# Ref_2V048_LM4132AMF.net
KiCad netlist of a schematic drawn in Altium Designer
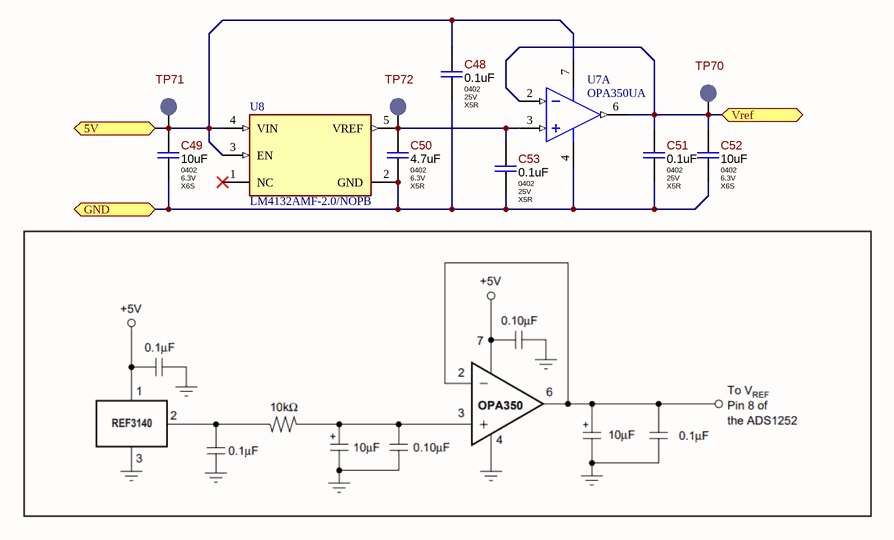
[diagram p0: Ref_2V048_LM4132AMF.SchDoc]

(export (version "E")
  (design (tool "Eeschema 10.0.6"))
  (components
    (comp (ref "C48")
      (value "0.1uF")
      (footprint "C_CERAMIC_0402_MED")
      (description "100nF 25V X5R ±10% 0402 Ceramic Capacitor RoHS")
      (fields
        (field (name "PACKAGE") "0402")
        (field (name "VOLTAGE") "25V")
        (field (name "DIELECTRIC TYPE") "X5R")
        (field (name "PART NUMBER") "CL05A104KA5NNNC")
        (field (name "MANUFACTURER") "Samsung Electro-Mechanics")
      )
      (libsource (lib "EL.XXX.T01") (part "Capacitor-NonPolar"))
    )
    (comp (ref "C49")
      (value "10uF")
      (footprint "C_CERAMIC_0402_MED")
      (description "10uF 6.3V X6S ±20% 0402 Ceramic Capacitor RoHS")
      (fields
        (field (name "PACKAGE") "0402")
        (field (name "VOLTAGE") "6.3V")
        (field (name "DIELECTRIC TYPE") "X6S")
        (field (name "PART NUMBER") "GRM155C80J106ME11D")
        (field (name "MANUFACTURER") "Murata Electronics")
      )
      (libsource (lib "EL.XXX.T01") (part "Capacitor-NonPolar"))
    )
    (comp (ref "C50")
      (value "4.7uF")
      (footprint "C_CERAMIC_0402_MED")
      (description "4.7uF 6.3V X5R ±20% 0402 Ceramic Capacitor RoHS")
      (fields
        (field (name "PACKAGE") "0402")
        (field (name "VOLTAGE") "6.3V")
        (field (name "DIELECTRIC TYPE") "X5R")
        (field (name "PART NUMBER") "GRM155R60J475ME47")
        (field (name "MANUFACTURER") "Murata Electronics")
      )
      (libsource (lib "EL.XXX.T01") (part "Capacitor-NonPolar"))
    )
    (comp (ref "C51")
      (value "0.1uF")
      (footprint "C_CERAMIC_0402_MED")
      (description "100nF 25V X5R ±10% 0402 Ceramic Capacitor RoHS")
      (fields
        (field (name "PACKAGE") "0402")
        (field (name "VOLTAGE") "25V")
        (field (name "DIELECTRIC TYPE") "X5R")
        (field (name "PART NUMBER") "CL05A104KA5NNNC")
        (field (name "MANUFACTURER") "Samsung Electro-Mechanics")
      )
      (libsource (lib "EL.XXX.T01") (part "Capacitor-NonPolar"))
    )
    (comp (ref "C52")
      (value "10uF")
      (footprint "C_CERAMIC_0402_MED")
      (description "10uF 6.3V X6S ±20% 0402 Ceramic Capacitor RoHS")
      (fields
        (field (name "PACKAGE") "0402")
        (field (name "VOLTAGE") "6.3V")
        (field (name "DIELECTRIC TYPE") "X6S")
        (field (name "PART NUMBER") "GRM155C80J106ME11D")
        (field (name "MANUFACTURER") "Murata Electronics")
      )
      (libsource (lib "EL.XXX.T01") (part "Capacitor-NonPolar"))
    )
    (comp (ref "C53")
      (value "0.1uF")
      (footprint "C_CERAMIC_0402_MED")
      (description "100nF 25V X5R ±10% 0402 Ceramic Capacitor RoHS")
      (fields
        (field (name "PACKAGE") "0402")
        (field (name "VOLTAGE") "25V")
        (field (name "DIELECTRIC TYPE") "X5R")
        (field (name "PART NUMBER") "CL05A104KA5NNNC")
        (field (name "MANUFACTURER") "Samsung Electro-Mechanics")
      )
      (libsource (lib "EL.XXX.T01") (part "Capacitor-NonPolar"))
    )
    (comp (ref "TP70")
      (value "LED_LINK")
      (footprint "TP_SMD_2mm")
      (description "Test Point SMD Pad 1.0mm/1.5mm/2mm")
      (fields (field (name "PART NUMBER") "TP-PAD-SMD"))
      (libsource (lib "EL.XXX.T01") (part "Test-Point-SMD-1"))
    )
    (comp (ref "TP71")
      (value "LED_LINK")
      (footprint "TP_SMD_2mm")
      (description "Test Point SMD Pad 1.0mm/1.5mm/2mm")
      (fields (field (name "PART NUMBER") "TP-PAD-SMD"))
      (libsource (lib "EL.XXX.T01") (part "Test-Point-SMD-1"))
    )
    (comp (ref "TP72")
      (value "LED_LINK")
      (footprint "TP_SMD_2mm")
      (description "Test Point SMD Pad 1.0mm/1.5mm/2mm")
      (fields (field (name "PART NUMBER") "TP-PAD-SMD"))
      (libsource (lib "EL.XXX.T01") (part "Test-Point-SMD-1"))
    )
    (comp (ref "U7")
      (value "OPA350UA")
      (footprint "D0008A_M")
      (fields (field (name "MANUFACTURER") "Texas Instruments"))
      (libsource (lib "EL.XXX.T01") (part "TI-OPA-8_1"))
    )
    (comp (ref "U8")
      (value "LM4132AMF-2.0/NOPB")
      (footprint "SOT-23-5")
      (description "IC VREF SERIES 0.05% SOT23-5")
      (fields (field (name "TOLERANCE") "0.05%"))
      (libsource (lib "EL.XXX.T01") (part "LM4132AMF-2.0/NOPB"))
    )
  )
  (nets
    (net (code "1") (name "/5V") (class "Default")
      (node (ref "C48") (pin "1") (pinfunction "1_1") (pintype "passive"))
      (node (ref "C49") (pin "1") (pinfunction "1_1") (pintype "passive"))
      (node (ref "TP71") (pin "1") (pintype "passive"))
      (node (ref "U7") (pin "7") (pinfunction "V+_7") (pintype "power_in"))
      (node (ref "U8") (pin "3") (pinfunction "EN_3") (pintype "input"))
      (node (ref "U8") (pin "4") (pinfunction "VIN_4") (pintype "input"))
    )
    (net (code "2") (name "/GND") (class "Default")
      (node (ref "C48") (pin "2") (pinfunction "2_2") (pintype "passive"))
      (node (ref "C49") (pin "2") (pinfunction "2_2") (pintype "passive"))
      (node (ref "C50") (pin "2") (pinfunction "2_2") (pintype "passive"))
      (node (ref "C51") (pin "2") (pinfunction "2_2") (pintype "passive"))
      (node (ref "C52") (pin "2") (pinfunction "2_2") (pintype "passive"))
      (node (ref "C53") (pin "2") (pinfunction "2_2") (pintype "passive"))
      (node (ref "U7") (pin "4") (pinfunction "V-_4") (pintype "power_in"))
      (node (ref "U8") (pin "2") (pinfunction "GND_2") (pintype "power_in"))
    )
    (net (code "3") (name "/Vref") (class "Default")
      (node (ref "C51") (pin "1") (pinfunction "1_1") (pintype "passive"))
      (node (ref "C52") (pin "1") (pinfunction "1_1") (pintype "passive"))
      (node (ref "TP70") (pin "1") (pintype "passive"))
      (node (ref "U7") (pin "2") (pinfunction "IN-_2") (pintype "input"))
      (node (ref "U7") (pin "6") (pinfunction "OUT_6") (pintype "output"))
    )
    (net (code "4") (name "Net-(U7A-IN+)") (class "Default")
      (node (ref "C50") (pin "1") (pinfunction "1_1") (pintype "passive"))
      (node (ref "C53") (pin "1") (pinfunction "1_1") (pintype "passive"))
      (node (ref "TP72") (pin "1") (pintype "passive"))
      (node (ref "U7") (pin "3") (pinfunction "IN+_3") (pintype "input"))
      (node (ref "U8") (pin "5") (pinfunction "VREF_5") (pintype "output"))
    )
    (net (code "5") (name "unconnected-(U8-NC-Pad1)") (class "Default")
      (node (ref "U8") (pin "1") (pinfunction "NC_1") (pintype "passive+no_connect"))
    )
  )
)
